# H01R0_Frontend.net
KiCad netlist of a schematic drawn in Altium Designer
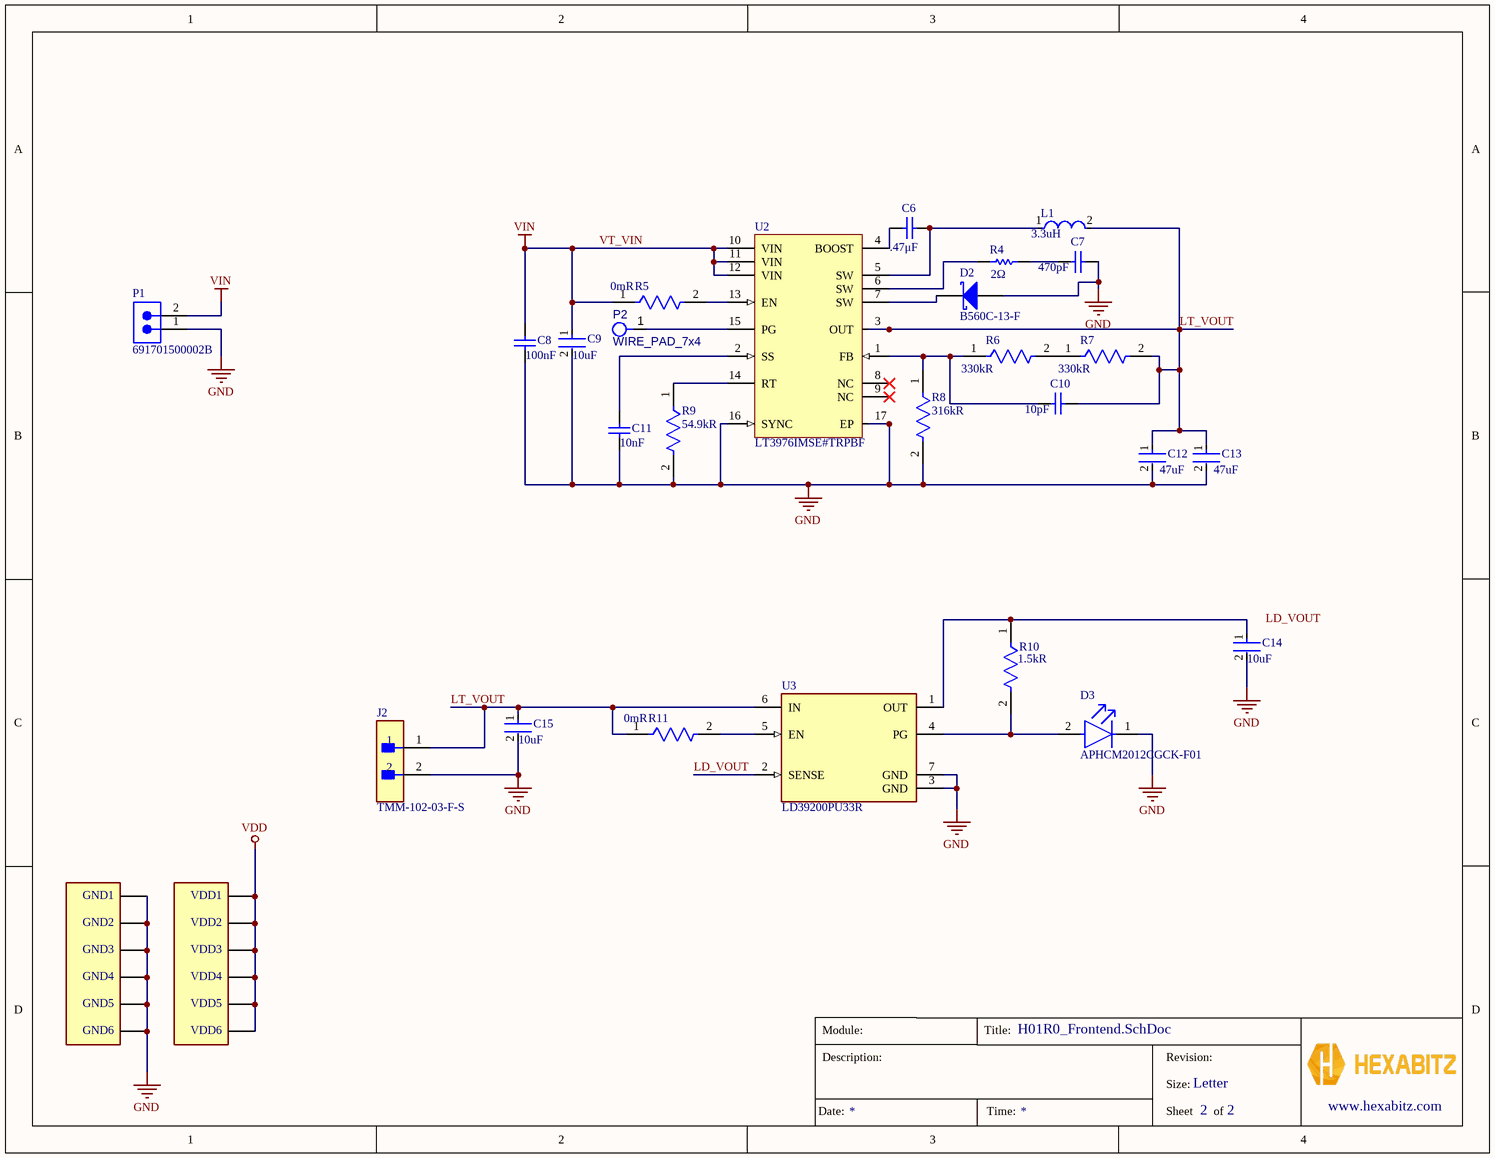
[diagram p0: H01R0_Frontend.SchDoc]

(export (version "E")
  (design (tool "Eeschema 10.0.6"))
  (components
    (comp (ref "C6")
      (value "VJ0805Y474KXQRW1BC")
      (footprint "CAPC2013X145X50LL20T20")
      (fields (field (name "MANUFACTURER") "Vitramon") (field (name "CAPACITANCE") ".47μF"))
      (libsource (lib "Altium Content Vault") (part "CAP"))
    )
    (comp (ref "C7")
      (value "08055C471KAT4A")
      (footprint "CAPC2013X94X50NL20T25")
      (fields (field (name "MANUFACTURER") "AVX Interconnect / Elco") (field (name "CAPACITANCE") "470pF"))
      (libsource (lib "Altium Content Vault") (part "CAP"))
    )
    (comp (ref "C8")
      (value "08055C104KAZ2A")
      (footprint "CAPC2013X94X50NL20T25")
      (fields (field (name "MANUFACTURER") "AVX Interconnect / Elco") (field (name "CAPACITANCE") "100nF"))
      (libsource (lib "Altium Content Vault") (part "CAP"))
    )
    (comp (ref "C9")
      (value "GRM32ER71H106KA12L")
      (footprint "FP-GRM32-MFG")
      (description "10µF ±10% 50V Ceramic Capacitor X7R 1210 (3225 Metric)")
      (fields (field (name "TOLERANCE") "10%") (field (name "CAPACITANCE") "10uF"))
      (libsource (lib "Altium Content Vault") (part "11868f565c42a9108669ba33697ecf6"))
    )
    (comp (ref "C10")
      (value "08051A100JAT4A")
      (footprint "CAPC2013X94X50LL20T25")
      (fields (field (name "MANUFACTURER") "AVX Interconnect / Elco") (field (name "CAPACITANCE") "10pF"))
      (libsource (lib "Altium Content Vault") (part "CAP"))
    )
    (comp (ref "C11")
      (value "0805YC103MAT2A")
      (footprint "CAPC2013X94X50ML20T25")
      (fields (field (name "MANUFACTURER") "AVX Interconnect / Elco") (field (name "CAPACITANCE") "10nF"))
      (libsource (lib "Altium Content Vault") (part "CAP"))
    )
    (comp (ref "C12")
      (value "GRM32ED71A476KE15L")
      (footprint "FP-GRM32E-0_3-0_2-MFG")
      (description "Chip Multilayer Ceramic Capacitors for General Purpose, 1210, 47uF, X7T, +22%/-33%, 10%, 10V")
      (fields (field (name "TOLERANCE") "10%") (field (name "CAPACITANCE") "47uF"))
      (libsource (lib "Altium Content Vault") (part "02cd4be3c70576c341d710602a673aa"))
    )
    (comp (ref "C13")
      (value "GRM32ED71A476KE15L")
      (footprint "FP-GRM32E-0_3-0_2-MFG")
      (description "Chip Multilayer Ceramic Capacitors for General Purpose, 1210, 47uF, X7T, +22%/-33%, 10%, 10V")
      (fields (field (name "TOLERANCE") "10%") (field (name "CAPACITANCE") "47uF"))
      (libsource (lib "Altium Content Vault") (part "02cd4be3c70576c341d710602a673aa"))
    )
    (comp (ref "C14")
      (value "GRM32ER71H106KA12L")
      (footprint "FP-GRM32-MFG")
      (description "10µF ±10% 50V Ceramic Capacitor X7R 1210 (3225 Metric)")
      (fields (field (name "TOLERANCE") "10%") (field (name "CAPACITANCE") "10uF"))
      (libsource (lib "Altium Content Vault") (part "11868f565c42a9108669ba33697ecf6"))
    )
    (comp (ref "C15")
      (value "GRM32ER71H106KA12L")
      (footprint "FP-GRM32-MFG")
      (description "10µF ±10% 50V Ceramic Capacitor X7R 1210 (3225 Metric)")
      (fields (field (name "TOLERANCE") "10%") (field (name "CAPACITANCE") "10uF"))
      (libsource (lib "Altium Content Vault") (part "11868f565c42a9108669ba33697ecf6"))
    )
    (comp (ref "D2")
      (value "B560C-13-F")
      (footprint "DIOD-B5X0C-2_M")
      (description "Schottky Barrier Rectifier, 5 A, 60 V, -55 to 125 degC, 2-Pin SMD, RoHS, Tape and Reel")
      (fields (field (name "MANUFACTURER") "DiodesIncorporated"))
      (libsource (lib "Altium Content Vault") (part "DSKY-KA-2"))
    )
    (comp (ref "D3")
      (value "APHCM2012CGCK-F01")
      (footprint "FP-APHCM2012CGCK-F01-MFG")
      (description "LED GREEN CLEAR CHIP SMD")
      (libsource (lib "Altium Content Vault") (part "8706943c75ba83719d021d2fdc84c58"))
    )
    (comp (ref "GND1")
      (value "HEXABIT_UART_PORT")
      (footprint "HEXABIT_POWER_PORT_D")
      (libsource (lib "hexabitz_connectors.Library") (part "HEXABIT_POWER_PORT_D"))
    )
    (comp (ref "GND2")
      (value "HEXABIT_UART_PORT")
      (footprint "HEXABIT_POWER_PORT_D")
      (libsource (lib "hexabitz_connectors.Library") (part "HEXABIT_POWER_PORT_D"))
    )
    (comp (ref "GND3")
      (value "HEXABIT_UART_PORT")
      (footprint "HEXABIT_POWER_PORT_D")
      (libsource (lib "hexabitz_connectors.Library") (part "HEXABIT_POWER_PORT_D"))
    )
    (comp (ref "GND4")
      (value "HEXABIT_UART_PORT")
      (footprint "HEXABIT_POWER_PORT_D")
      (libsource (lib "hexabitz_connectors.Library") (part "HEXABIT_POWER_PORT_D"))
    )
    (comp (ref "GND5")
      (value "HEXABIT_UART_PORT")
      (footprint "HEXABIT_POWER_PORT_D")
      (libsource (lib "hexabitz_connectors.Library") (part "HEXABIT_POWER_PORT_D"))
    )
    (comp (ref "GND6")
      (value "HEXABIT_UART_PORT")
      (footprint "HEXABIT_POWER_PORT_D")
      (libsource (lib "hexabitz_connectors.Library") (part "HEXABIT_POWER_PORT_D"))
    )
    (comp (ref "J2")
      (value "TMM-102-03-F-S")
      (footprint "FP-TMM-102-03-F-S-MFG")
      (description "CONN HEADER VERT 2POS 2MM")
      (libsource (lib "Altium Content Vault") (part "3bc925449376181038e59eaffc5286c"))
    )
    (comp (ref "L1")
      (value "MLZ2012A3R3WT000")
      (footprint "FP-MLZ2012-0_85-IPC_C")
      (description "Shielded Multilayer Inductor 3.3uH ±20% 450mA 442mΩ SMD 0805")
      (fields (field (name "INDUCTANCE") "3.3uH") (field (name "TOLERANCE") "20%"))
      (libsource (lib "Altium Content Vault") (part "725321dda6339637d4d059423bc1c3c"))
    )
    (comp (ref "P1")
      (value "691701500002B")
      (footprint "691701500002B")
      (libsource (lib "Altium Content Vault") (part "TBL - 1R - 02P - Male"))
    )
    (comp (ref "P2")
      (value "WIRE_PAD_7x4")
      (footprint "WIRE_PAD_7x4-Footprint-1")
      (description "SMD WIRE PAD 7 x 4 mm")
      (libsource (lib "Nathan Price") (part "CMP-001-0023-7"))
    )
    (comp (ref "R4")
      (value "CRCW08052R00FNEA")
      (footprint "RESC2013X50X30NL20T20")
      (fields (field (name "MANUFACTURER") "Vishay Dale") (field (name "RESISTANCE") "2Ω"))
      (libsource (lib "Altium Content Vault") (part "RES"))
    )
    (comp (ref "R5")
      (value "RMCF0805ZT0R00")
      (footprint "FP-RMCF0805-MFG")
      (description "RES 0 OHM JUMPER 1/8W 0805")
      (fields (field (name "RESISTANCE") "0mR"))
      (libsource (lib "Altium Content Vault") (part "1029c3af85768c4190bb7ad29bc67b5"))
    )
    (comp (ref "R6")
      (value "CRCW0805330KFKEA")
      (footprint "FP-CRCW0805-e3-MFG")
      (description "RES Thick Film, 330kΩ, 1%, 0.125W, 100ppm/°C, 0805")
      (fields (field (name "RESISTANCE") "330kR") (field (name "TOLERANCE") "1%"))
      (libsource (lib "Altium Content Vault") (part "1029c3af85768c4190bb7ad29bc67b5"))
    )
    (comp (ref "R7")
      (value "CRCW0805330KFKEA")
      (footprint "FP-CRCW0805-e3-MFG")
      (description "RES Thick Film, 330kΩ, 1%, 0.125W, 100ppm/°C, 0805")
      (fields (field (name "RESISTANCE") "330kR") (field (name "TOLERANCE") "1%"))
      (libsource (lib "Altium Content Vault") (part "1029c3af85768c4190bb7ad29bc67b5"))
    )
    (comp (ref "R8")
      (value "RC2012F3163CS")
      (footprint "FP-RC2012-IPC_C")
      (description "Res Thick Film 0805 316kΩ 1% 0.125W ±100ppm/°C Molded SMD T/R")
      (fields (field (name "TOLERANCE") "1%") (field (name "RESISTANCE") "316kR"))
      (libsource (lib "Altium Content Vault") (part "1029c3af85768c4190bb7ad29bc67b5"))
    )
    (comp (ref "R9")
      (value "CR0805-FX-5492ELF")
      (footprint "FP-CR0805-MFG")
      (description "Thick Film Chip Resistors 0805 54.9kΩ 0.125W 1% 100ppm/°C")
      (fields (field (name "RESISTANCE") "54.9kR") (field (name "TOLERANCE") "1%"))
      (libsource (lib "Altium Content Vault") (part "1029c3af85768c4190bb7ad29bc67b5"))
    )
    (comp (ref "R10")
      (value "RMCF0805JT1K50")
      (footprint "FP-RMCF0805-IPC_A")
      (description "1.5kΩ ±5% 0.125W 0805 Thick Film Chip Resistor AEC-Q200 compliant")
      (fields (field (name "TOLERANCE") "5%") (field (name "RESISTANCE") "1.5kR"))
      (libsource (lib "Altium Content Vault") (part "1029c3af85768c4190bb7ad29bc67b5"))
    )
    (comp (ref "R11")
      (value "RMCF0805ZT0R00")
      (footprint "FP-RMCF0805-MFG")
      (description "RES 0 OHM JUMPER 1/8W 0805")
      (fields (field (name "RESISTANCE") "0mR"))
      (libsource (lib "Altium Content Vault") (part "1029c3af85768c4190bb7ad29bc67b5"))
    )
    (comp (ref "U2")
      (value "LT3976IMSE#TRPBF")
      (footprint "LT-MSE-16-EDP_M")
      (description "LT3976 - 40V, 5A, 2MHz Step-Down Switching Regulator with 3.3μA Quiescent Current")
      (libsource (lib "Nathan Price") (part "LT-LT3975_LT3976-MSE-16"))
    )
    (comp (ref "U3")
      (value "LD39200PU33R")
      (footprint "FP-DFN6-7946637-MFG")
      (description "IC REG LINEAR 3.3V 2A 6DFN")
      (libsource (lib "Altium Content Vault") (part "f0cfe00d12cb984572f50007c934a2d"))
    )
    (comp (ref "VDD1")
      (value "HEXABIT_UART_PORT")
      (footprint "HEXABIT_POWER_PORT_U")
      (libsource (lib "hexabitz_connectors.Library") (part "HEXABIT_POWER_PORT_U"))
    )
    (comp (ref "VDD2")
      (value "HEXABIT_UART_PORT")
      (footprint "HEXABIT_POWER_PORT_U")
      (libsource (lib "hexabitz_connectors.Library") (part "HEXABIT_POWER_PORT_U"))
    )
    (comp (ref "VDD3")
      (value "HEXABIT_UART_PORT")
      (footprint "HEXABIT_POWER_PORT_U")
      (libsource (lib "hexabitz_connectors.Library") (part "HEXABIT_POWER_PORT_U"))
    )
    (comp (ref "VDD4")
      (value "HEXABIT_UART_PORT")
      (footprint "HEXABIT_POWER_PORT_U")
      (libsource (lib "hexabitz_connectors.Library") (part "HEXABIT_POWER_PORT_U"))
    )
    (comp (ref "VDD5")
      (value "HEXABIT_UART_PORT")
      (footprint "HEXABIT_POWER_PORT_U")
      (libsource (lib "hexabitz_connectors.Library") (part "HEXABIT_POWER_PORT_U"))
    )
    (comp (ref "VDD6")
      (value "HEXABIT_UART_PORT")
      (footprint "HEXABIT_POWER_PORT_U")
      (libsource (lib "hexabitz_connectors.Library") (part "HEXABIT_POWER_PORT_U"))
    )
  )
  (nets
    (net (code "1") (name "/LD_VOUT") (class "Default")
      (node (ref "U3") (pin "2") (pinfunction "SENSE_2") (pintype "input"))
    )
    (net (code "2") (name "/LT_VOUT") (class "Default")
      (node (ref "C10") (pin "2") (pinfunction "2_2") (pintype "passive"))
      (node (ref "C12") (pin "1") (pinfunction "1_1") (pintype "passive"))
      (node (ref "C13") (pin "1") (pinfunction "1_1") (pintype "passive"))
      (node (ref "C15") (pin "1") (pinfunction "1_1") (pintype "passive"))
      (node (ref "J2") (pin "1") (pinfunction "1_1") (pintype "passive"))
      (node (ref "L1") (pin "2") (pinfunction "2_2") (pintype "passive"))
      (node (ref "R11") (pin "1") (pinfunction "1_1") (pintype "passive"))
      (node (ref "R7") (pin "2") (pinfunction "2_2") (pintype "passive"))
      (node (ref "U2") (pin "3") (pinfunction "OUT_3") (pintype "power_in"))
      (node (ref "U3") (pin "6") (pinfunction "IN_6") (pintype "power_in"))
    )
    (net (code "3") (name "GND") (class "Default")
      (node (ref "C11") (pin "2") (pinfunction "2_2") (pintype "passive"))
      (node (ref "C12") (pin "2") (pinfunction "2_2") (pintype "passive"))
      (node (ref "C13") (pin "2") (pinfunction "2_2") (pintype "passive"))
      (node (ref "C14") (pin "2") (pinfunction "2_2") (pintype "passive"))
      (node (ref "C15") (pin "2") (pinfunction "2_2") (pintype "passive"))
      (node (ref "C7") (pin "2") (pinfunction "2_2") (pintype "passive"))
      (node (ref "C8") (pin "2") (pinfunction "2_2") (pintype "passive"))
      (node (ref "C9") (pin "2") (pinfunction "2_2") (pintype "passive"))
      (node (ref "D2") (pin "2") (pinfunction "A_2") (pintype "passive"))
      (node (ref "D3") (pin "1") (pinfunction "C_1") (pintype "passive"))
      (node (ref "GND1") (pin "Pwr_D") (pinfunction "Pwr_D_Pwr_D") (pintype "passive"))
      (node (ref "GND2") (pin "Pwr_D") (pinfunction "Pwr_D_Pwr_D") (pintype "passive"))
      (node (ref "GND3") (pin "Pwr_D") (pinfunction "Pwr_D_Pwr_D") (pintype "passive"))
      (node (ref "GND4") (pin "Pwr_D") (pinfunction "Pwr_D_Pwr_D") (pintype "passive"))
      (node (ref "GND5") (pin "Pwr_D") (pinfunction "Pwr_D_Pwr_D") (pintype "passive"))
      (node (ref "GND6") (pin "Pwr_D") (pinfunction "Pwr_D_Pwr_D") (pintype "passive"))
      (node (ref "J2") (pin "2") (pinfunction "2_2") (pintype "passive"))
      (node (ref "P1") (pin "1") (pinfunction "1_1") (pintype "passive"))
      (node (ref "R8") (pin "2") (pinfunction "2_2") (pintype "passive"))
      (node (ref "R9") (pin "2") (pinfunction "2_2") (pintype "passive"))
      (node (ref "U2") (pin "16") (pinfunction "SYNC_16") (pintype "input"))
      (node (ref "U2") (pin "17") (pinfunction "EP_17") (pintype "power_in"))
      (node (ref "U3") (pin "3") (pinfunction "GND_3") (pintype "power_in"))
      (node (ref "U3") (pin "7") (pinfunction "GND_7") (pintype "power_in"))
    )
    (net (code "4") (name "Net-(C6-Pad1)") (class "Default")
      (node (ref "C6") (pin "1") (pinfunction "1_1") (pintype "passive"))
      (node (ref "L1") (pin "1") (pinfunction "1_1") (pintype "passive"))
      (node (ref "U2") (pin "5") (pinfunction "SW_5") (pintype "power_in"))
    )
    (net (code "5") (name "Net-(C7-Pad1)") (class "Default")
      (node (ref "C7") (pin "1") (pinfunction "1_1") (pintype "passive"))
      (node (ref "R4") (pin "1") (pinfunction "1_1") (pintype "passive"))
    )
    (net (code "6") (name "Net-(D2-K)") (class "Default")
      (node (ref "D2") (pin "1") (pinfunction "K_1") (pintype "passive"))
      (node (ref "U2") (pin "7") (pinfunction "SW_7") (pintype "power_in"))
    )
    (net (code "7") (name "Net-(D3-A)") (class "Default")
      (node (ref "D3") (pin "2") (pinfunction "A_2") (pintype "passive"))
      (node (ref "R10") (pin "2") (pinfunction "2_2") (pintype "passive"))
      (node (ref "U3") (pin "4") (pinfunction "PG_4") (pintype "open_collector"))
    )
    (net (code "8") (name "Net-(P2-H1)") (class "Default")
      (node (ref "P2") (pin "1") (pinfunction "H1_1") (pintype "passive"))
      (node (ref "U2") (pin "15") (pinfunction "PG_15") (pintype "tri_state"))
    )
    (net (code "9") (name "Net-(R4-Pad2)") (class "Default")
      (node (ref "R4") (pin "2") (pinfunction "2_2") (pintype "passive"))
      (node (ref "U2") (pin "6") (pinfunction "SW_6") (pintype "power_in"))
    )
    (net (code "10") (name "Net-(R6-Pad2)") (class "Default")
      (node (ref "R6") (pin "2") (pinfunction "2_2") (pintype "passive"))
      (node (ref "R7") (pin "1") (pinfunction "1_1") (pintype "passive"))
    )
    (net (code "11") (name "Net-(U2-BOOST)") (class "Default")
      (node (ref "C6") (pin "2") (pinfunction "2_2") (pintype "passive"))
      (node (ref "U2") (pin "4") (pinfunction "BOOST_4") (pintype "passive"))
    )
    (net (code "12") (name "Net-(U2-EN)") (class "Default")
      (node (ref "R5") (pin "2") (pinfunction "2_2") (pintype "passive"))
      (node (ref "U2") (pin "13") (pinfunction "EN_13") (pintype "input"))
    )
    (net (code "13") (name "Net-(U2-FB)") (class "Default")
      (node (ref "C10") (pin "1") (pinfunction "1_1") (pintype "passive"))
      (node (ref "R6") (pin "1") (pinfunction "1_1") (pintype "passive"))
      (node (ref "R8") (pin "1") (pinfunction "1_1") (pintype "passive"))
      (node (ref "U2") (pin "1") (pinfunction "FB_1") (pintype "input"))
    )
    (net (code "14") (name "Net-(U2-RT)") (class "Default")
      (node (ref "R9") (pin "1") (pinfunction "1_1") (pintype "passive"))
      (node (ref "U2") (pin "14") (pinfunction "RT_14") (pintype "passive"))
    )
    (net (code "15") (name "Net-(U2-SS)") (class "Default")
      (node (ref "C11") (pin "1") (pinfunction "1_1") (pintype "passive"))
      (node (ref "U2") (pin "2") (pinfunction "SS_2") (pintype "input"))
    )
    (net (code "16") (name "Net-(U3-EN)") (class "Default")
      (node (ref "R11") (pin "2") (pinfunction "2_2") (pintype "passive"))
      (node (ref "U3") (pin "5") (pinfunction "EN_5") (pintype "input"))
    )
    (net (code "17") (name "Net-(U3-OUT)") (class "Default")
      (node (ref "C14") (pin "1") (pinfunction "1_1") (pintype "passive"))
      (node (ref "R10") (pin "1") (pinfunction "1_1") (pintype "passive"))
      (node (ref "U3") (pin "1") (pinfunction "OUT_1") (pintype "power_in"))
    )
    (net (code "18") (name "VDD") (class "Default")
      (node (ref "VDD1") (pin "Pwr_U") (pinfunction "Pwr_U_Pwr_U") (pintype "passive"))
      (node (ref "VDD2") (pin "Pwr_U") (pinfunction "Pwr_U_Pwr_U") (pintype "passive"))
      (node (ref "VDD3") (pin "Pwr_U") (pinfunction "Pwr_U_Pwr_U") (pintype "passive"))
      (node (ref "VDD4") (pin "Pwr_U") (pinfunction "Pwr_U_Pwr_U") (pintype "passive"))
      (node (ref "VDD5") (pin "Pwr_U") (pinfunction "Pwr_U_Pwr_U") (pintype "passive"))
      (node (ref "VDD6") (pin "Pwr_U") (pinfunction "Pwr_U_Pwr_U") (pintype "passive"))
    )
    (net (code "19") (name "VIN") (class "Default")
      (node (ref "C8") (pin "1") (pinfunction "1_1") (pintype "passive"))
      (node (ref "C9") (pin "1") (pinfunction "1_1") (pintype "passive"))
      (node (ref "P1") (pin "2") (pinfunction "2_2") (pintype "passive"))
      (node (ref "R5") (pin "1") (pinfunction "1_1") (pintype "passive"))
      (node (ref "U2") (pin "10") (pinfunction "VIN_10") (pintype "power_in"))
      (node (ref "U2") (pin "11") (pinfunction "VIN_11") (pintype "power_in"))
      (node (ref "U2") (pin "12") (pinfunction "VIN_12") (pintype "power_in"))
    )
    (net (code "20") (name "unconnected-(U2-NC-Pad8)") (class "Default")
      (node (ref "U2") (pin "8") (pinfunction "NC_8") (pintype "passive+no_connect"))
    )
    (net (code "21") (name "unconnected-(U2-NC-Pad9)") (class "Default")
      (node (ref "U2") (pin "9") (pinfunction "NC_9") (pintype "passive+no_connect"))
    )
  )
)
